# RC_Interface.net
KiCad netlist of a schematic drawn in Altium Designer
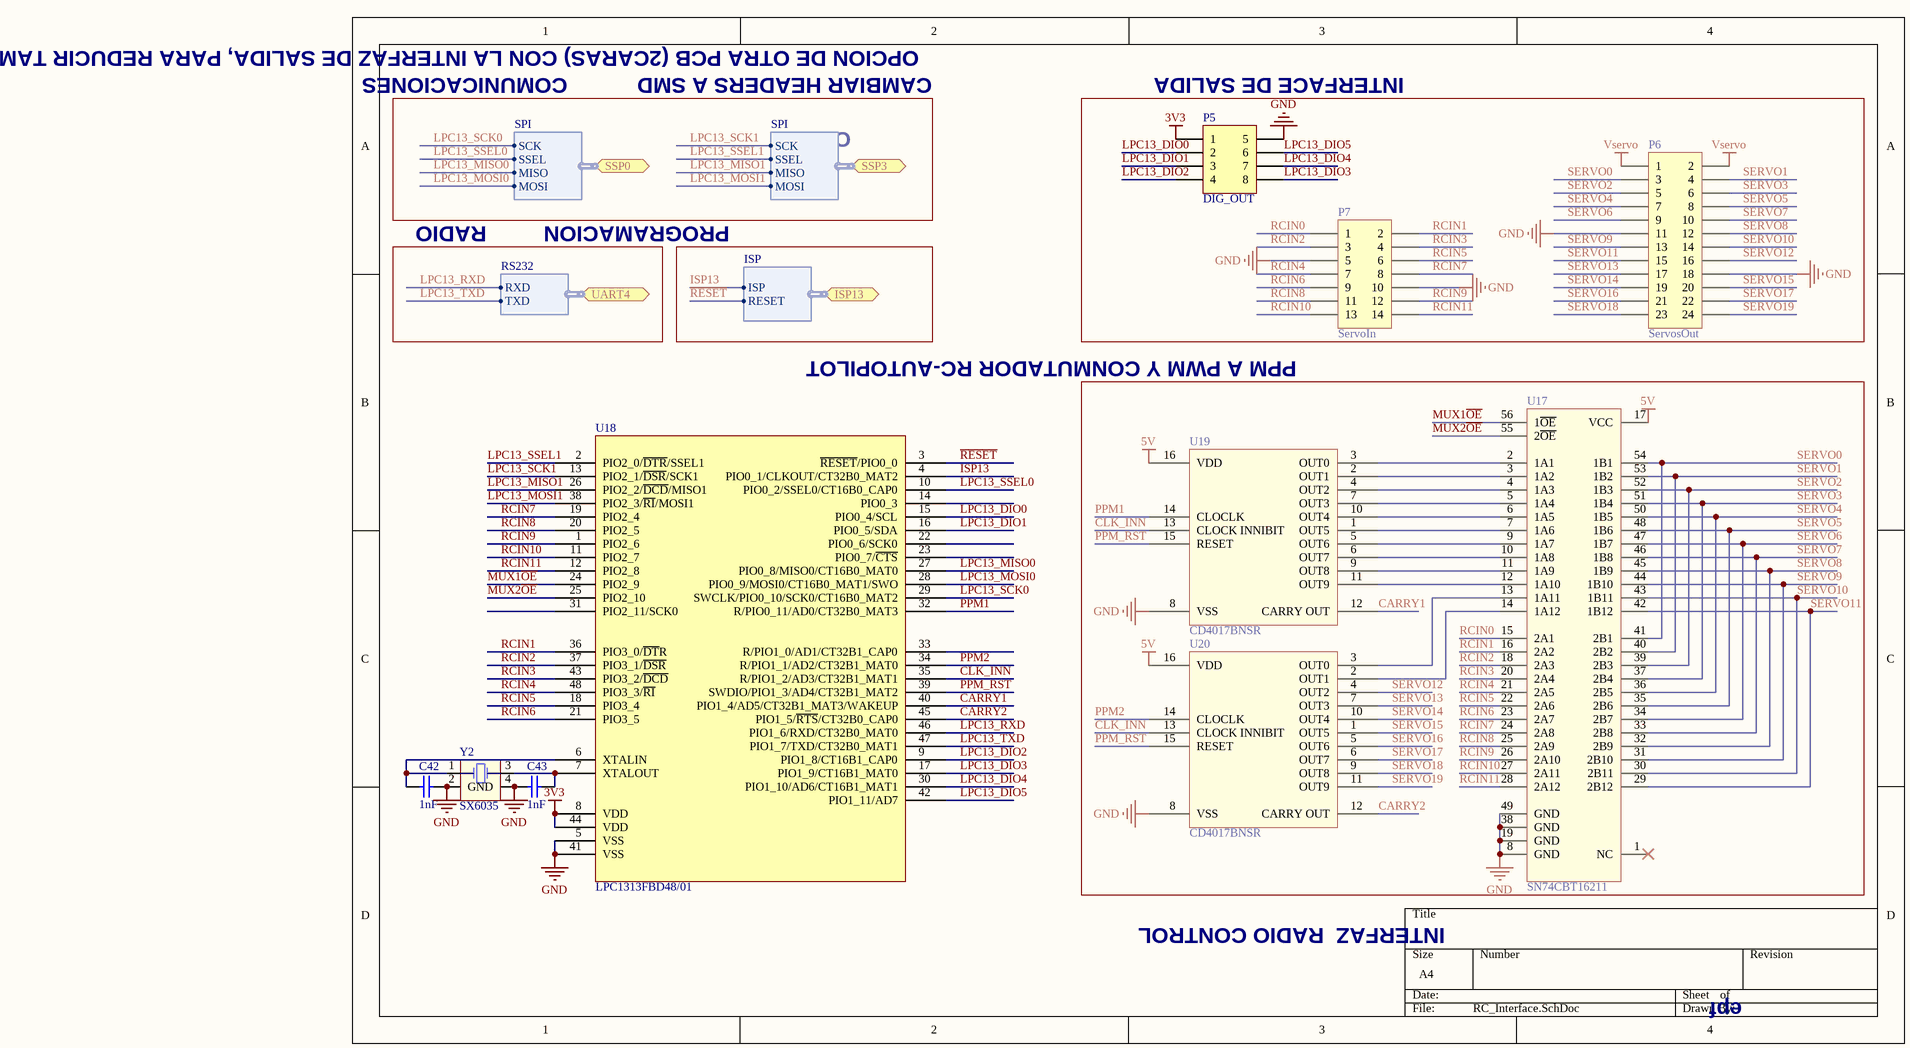
[diagram p0: RC_Interface.SchDoc]

(export (version "E")
  (design (tool "Eeschema 10.0.6"))
  (components
    (comp (ref "C42")
      (value "1nF")
      (footprint "CAP0402")
      (fields (field (name "Comment") "Capacitor"))
      (libsource (lib "epf") (part "Cap"))
    )
    (comp (ref "C43")
      (value "1nF")
      (footprint "CAP0402")
      (fields (field (name "Comment") "Capacitor"))
      (libsource (lib "epf") (part "Cap"))
    )
    (comp (ref "P5")
      (value "DIG_OUT")
      (footprint "HDR2X4_CEN")
      (description "Header, 4-Pin, Dual row")
      (fields (field (name "PUBLISHER") "Altium Limited"))
      (libsource (lib "epf") (part "AP_SALIDA_DIGITAL"))
    )
    (comp (ref "P6")
      (value "ServosOut")
      (footprint "HDR 2X12")
      (description "Header, 12-Pin, Dual row")
      (fields (field (name "PUBLISHER") "Altium Limited"))
      (libsource (lib "epf") (part "ServosOut"))
    )
    (comp (ref "P7")
      (value "ServoIn")
      (footprint "HDR2X7")
      (description "Header, 7-Pin, Dual row")
      (fields (field (name "PUBLISHER") "Altium Limited"))
      (libsource (lib "epf") (part "ServoIn"))
    )
    (comp (ref "U17")
      (value "SN74CBT16211")
      (footprint "SOP635P1035-56N")
      (description "MUX")
      (libsource (lib "epf") (part "SN74CBT16211"))
    )
    (comp (ref "U18")
      (value "LPC1313FBD48/01")
      (footprint "TQFP48_LPC1343")
      (description "ARM CortexM3 32K Flash, 8k RAM")
      (libsource (lib "epf") (part "LPC1313FBD48/01"))
    )
    (comp (ref "U19")
      (value "CD4017BNSR")
      (footprint "SOIC127P602-16BN")
      (description "COUNTER/DIVIDERS")
      (libsource (lib "epf") (part "CD4017BNSR"))
    )
    (comp (ref "U20")
      (value "CD4017BNSR")
      (footprint "SOIC127P602-16BN")
      (description "COUNTER/DIVIDERS")
      (libsource (lib "epf") (part "CD4017BNSR"))
    )
    (comp (ref "Y2") (value "SX6035") (footprint "SX6035") (libsource (lib "epf") (part "XTAL_SX6035")))
  )
  (nets
    (net (code "4") (name "/CARRY1") (class "Default")
      (node (ref "U18") (pin "40") (pinfunction "PIO1_4/AD5/CT32B1_MAT3/WAKEUP_40") (pintype "passive"))
      (node (ref "U19") (pin "12") (pinfunction "CARRY_OUT_12") (pintype "passive"))
    )
    (net (code "5") (name "/CARRY2") (class "Default")
      (node (ref "U18") (pin "45") (pinfunction "PIO1_5/~{RTS}/CT32B0_CAP0_45") (pintype "passive"))
      (node (ref "U20") (pin "12") (pinfunction "CARRY_OUT_12") (pintype "passive"))
    )
    (net (code "6") (name "/CLK_INN") (class "Default")
      (node (ref "U18") (pin "35") (pinfunction "R/PIO1_2/AD3/CT32B1_MAT1_35") (pintype "passive"))
      (node (ref "U19") (pin "13") (pinfunction "CLOCK_INNIBIT_13") (pintype "passive"))
      (node (ref "U20") (pin "13") (pinfunction "CLOCK_INNIBIT_13") (pintype "passive"))
    )
    (net (code "7") (name "/ISP13") (class "Default")
      (node (ref "U18") (pin "4") (pinfunction "PIO0_1/CLKOUT/CT32B0_MAT2_4") (pintype "passive"))
    )
    (net (code "8") (name "/LPC13_DIO0") (class "Default")
      (node (ref "P5") (pin "2") (pinfunction "2_2") (pintype "passive"))
      (node (ref "U18") (pin "15") (pinfunction "PIO0_4/SCL_15") (pintype "passive"))
    )
    (net (code "9") (name "/LPC13_DIO1") (class "Default")
      (node (ref "P5") (pin "3") (pinfunction "3_3") (pintype "passive"))
      (node (ref "U18") (pin "16") (pinfunction "PIO0_5/SDA_16") (pintype "passive"))
    )
    (net (code "10") (name "/LPC13_DIO2") (class "Default")
      (node (ref "P5") (pin "4") (pinfunction "4_4") (pintype "passive"))
      (node (ref "U18") (pin "9") (pinfunction "PIO1_8/CT16B1_CAP0_9") (pintype "passive"))
    )
    (net (code "11") (name "/LPC13_DIO3") (class "Default")
      (node (ref "P5") (pin "8") (pinfunction "8_8") (pintype "passive"))
      (node (ref "U18") (pin "17") (pinfunction "PIO1_9/CT16B1_MAT0_17") (pintype "passive"))
    )
    (net (code "12") (name "/LPC13_DIO4") (class "Default")
      (node (ref "P5") (pin "7") (pinfunction "7_7") (pintype "passive"))
      (node (ref "U18") (pin "30") (pinfunction "PIO1_10/AD6/CT16B1_MAT1_30") (pintype "passive"))
    )
    (net (code "13") (name "/LPC13_DIO5") (class "Default")
      (node (ref "P5") (pin "6") (pinfunction "6_6") (pintype "passive"))
      (node (ref "U18") (pin "42") (pinfunction "PIO1_11/AD7_42") (pintype "passive"))
    )
    (net (code "14") (name "/LPC13_MISO0") (class "Default")
      (node (ref "U18") (pin "27") (pinfunction "PIO0_8/MISO0/CT16B0_MAT0_27") (pintype "passive"))
    )
    (net (code "15") (name "/LPC13_MISO1") (class "Default")
      (node (ref "U18") (pin "26") (pinfunction "PIO2_2/~{DCD}/MISO1_26") (pintype "passive"))
    )
    (net (code "16") (name "/LPC13_MOSI0") (class "Default")
      (node (ref "U18") (pin "28") (pinfunction "PIO0_9/MOSI0/CT16B0_MAT1/SWO_28") (pintype "passive"))
    )
    (net (code "17") (name "/LPC13_MOSI1") (class "Default")
      (node (ref "U18") (pin "38") (pinfunction "PIO2_3/~{RI}/MOSI1_38") (pintype "passive"))
    )
    (net (code "18") (name "/LPC13_RXD") (class "Default")
      (node (ref "U18") (pin "46") (pinfunction "PIO1_6/RXD/CT32B0_MAT0_46") (pintype "passive"))
    )
    (net (code "19") (name "/LPC13_SCK0") (class "Default")
      (node (ref "U18") (pin "29") (pinfunction "SWCLK/PIO0_10/SCK0/CT16B0_MAT2_29") (pintype "passive"))
    )
    (net (code "20") (name "/LPC13_SCK1") (class "Default")
      (node (ref "U18") (pin "13") (pinfunction "PIO2_1/~{DSR}/SCK1_13") (pintype "passive"))
    )
    (net (code "21") (name "/LPC13_SSEL0") (class "Default")
      (node (ref "U18") (pin "10") (pinfunction "PIO0_2/SSEL0/CT16B0_CAP0_10") (pintype "passive"))
    )
    (net (code "22") (name "/LPC13_SSEL1") (class "Default")
      (node (ref "U18") (pin "2") (pinfunction "PIO2_0/~{DTR}/SSEL1_2") (pintype "passive"))
    )
    (net (code "23") (name "/LPC13_TXD") (class "Default")
      (node (ref "U18") (pin "47") (pinfunction "PIO1_7/TXD/CT32B0_MAT1_47") (pintype "passive"))
    )
    (net (code "24") (name "/MUX1~{OE}") (class "Default")
      (node (ref "U17") (pin "56") (pinfunction "1~{OE}_56") (pintype "passive"))
      (node (ref "U18") (pin "24") (pinfunction "PIO2_9_24") (pintype "passive"))
    )
    (net (code "25") (name "/MUX2~{OE}") (class "Default")
      (node (ref "U17") (pin "55") (pinfunction "2~{OE}_55") (pintype "passive"))
      (node (ref "U18") (pin "25") (pinfunction "PIO2_10_25") (pintype "passive"))
    )
    (net (code "26") (name "/PPM1") (class "Default")
      (node (ref "U18") (pin "32") (pinfunction "R/PIO0_11/AD0/CT32B0_MAT3_32") (pintype "passive"))
      (node (ref "U19") (pin "14") (pinfunction "CLOCLK_14") (pintype "passive"))
    )
    (net (code "27") (name "/PPM2") (class "Default")
      (node (ref "U18") (pin "34") (pinfunction "R/PIO1_1/AD2/CT32B1_MAT0_34") (pintype "passive"))
      (node (ref "U20") (pin "14") (pinfunction "CLOCLK_14") (pintype "passive"))
    )
    (net (code "28") (name "/PPM_RST") (class "Default")
      (node (ref "U18") (pin "39") (pinfunction "SWDIO/PIO1_3/AD4/CT32B1_MAT2_39") (pintype "passive"))
      (node (ref "U19") (pin "15") (pinfunction "RESET_15") (pintype "passive"))
      (node (ref "U20") (pin "15") (pinfunction "RESET_15") (pintype "passive"))
    )
    (net (code "29") (name "/RCIN0") (class "Default")
      (node (ref "P7") (pin "1") (pinfunction "1_1") (pintype "passive"))
      (node (ref "U17") (pin "15") (pinfunction "2A1_15") (pintype "passive"))
    )
    (net (code "30") (name "/RCIN1") (class "Default")
      (node (ref "P7") (pin "2") (pinfunction "2_2") (pintype "passive"))
      (node (ref "U17") (pin "16") (pinfunction "2A2_16") (pintype "passive"))
      (node (ref "U18") (pin "36") (pinfunction "PIO3_0/~{DT}R_36") (pintype "passive"))
    )
    (net (code "31") (name "/RCIN2") (class "Default")
      (node (ref "P7") (pin "3") (pinfunction "3_3") (pintype "passive"))
      (node (ref "U17") (pin "18") (pinfunction "2A3_18") (pintype "passive"))
      (node (ref "U18") (pin "37") (pinfunction "PIO3_1/~{DSR}_37") (pintype "passive"))
    )
    (net (code "32") (name "/RCIN3") (class "Default")
      (node (ref "P7") (pin "4") (pinfunction "4_4") (pintype "passive"))
      (node (ref "U17") (pin "20") (pinfunction "2A4_20") (pintype "passive"))
      (node (ref "U18") (pin "43") (pinfunction "PIO3_2/~{DCD}_43") (pintype "passive"))
    )
    (net (code "33") (name "/RCIN4") (class "Default")
      (node (ref "P7") (pin "7") (pinfunction "7_7") (pintype "passive"))
      (node (ref "U17") (pin "21") (pinfunction "2A5_21") (pintype "passive"))
      (node (ref "U18") (pin "48") (pinfunction "PIO3_3/~{RI}_48") (pintype "passive"))
    )
    (net (code "34") (name "/RCIN5") (class "Default")
      (node (ref "P7") (pin "6") (pinfunction "6_6") (pintype "passive"))
      (node (ref "U17") (pin "22") (pinfunction "2A6_22") (pintype "passive"))
      (node (ref "U18") (pin "18") (pinfunction "PIO3_4_18") (pintype "passive"))
    )
    (net (code "35") (name "/RCIN6") (class "Default")
      (node (ref "P7") (pin "9") (pinfunction "9_9") (pintype "passive"))
      (node (ref "U17") (pin "23") (pinfunction "2A7_23") (pintype "passive"))
      (node (ref "U18") (pin "21") (pinfunction "PIO3_5_21") (pintype "passive"))
    )
    (net (code "36") (name "/RCIN7") (class "Default")
      (node (ref "P7") (pin "8") (pinfunction "8_8") (pintype "passive"))
      (node (ref "U17") (pin "24") (pinfunction "2A8_24") (pintype "passive"))
      (node (ref "U18") (pin "19") (pinfunction "PIO2_4_19") (pintype "passive"))
    )
    (net (code "37") (name "/RCIN8") (class "Default")
      (node (ref "P7") (pin "11") (pinfunction "11_11") (pintype "passive"))
      (node (ref "U17") (pin "25") (pinfunction "2A9_25") (pintype "passive"))
      (node (ref "U18") (pin "20") (pinfunction "PIO2_5_20") (pintype "passive"))
    )
    (net (code "38") (name "/RCIN9") (class "Default")
      (node (ref "P7") (pin "12") (pinfunction "12_12") (pintype "passive"))
      (node (ref "U17") (pin "26") (pinfunction "2A10_26") (pintype "passive"))
      (node (ref "U18") (pin "1") (pinfunction "PIO2_6_1") (pintype "passive"))
    )
    (net (code "39") (name "/RCIN10") (class "Default")
      (node (ref "P7") (pin "13") (pinfunction "13_13") (pintype "passive"))
      (node (ref "U17") (pin "27") (pinfunction "2A11_27") (pintype "passive"))
      (node (ref "U18") (pin "11") (pinfunction "PIO2_7_11") (pintype "passive"))
    )
    (net (code "40") (name "/RCIN11") (class "Default")
      (node (ref "P7") (pin "14") (pinfunction "14_14") (pintype "passive"))
      (node (ref "U17") (pin "28") (pinfunction "2A12_28") (pintype "passive"))
      (node (ref "U18") (pin "12") (pinfunction "PIO2_8_12") (pintype "passive"))
    )
    (net (code "41") (name "/RESET") (class "Default")
      (node (ref "U18") (pin "3") (pinfunction "~{RESET}/PIO0_0_3") (pintype "passive"))
    )
    (net (code "42") (name "/SERVO0") (class "Default")
      (node (ref "P6") (pin "3") (pinfunction "3_3") (pintype "passive"))
      (node (ref "U17") (pin "41") (pinfunction "2B1_41") (pintype "passive"))
      (node (ref "U17") (pin "54") (pinfunction "1B1_54") (pintype "passive"))
    )
    (net (code "43") (name "/SERVO1") (class "Default")
      (node (ref "P6") (pin "4") (pinfunction "4_4") (pintype "passive"))
      (node (ref "U17") (pin "40") (pinfunction "2B2_40") (pintype "passive"))
      (node (ref "U17") (pin "53") (pinfunction "1B2_53") (pintype "passive"))
    )
    (net (code "44") (name "/SERVO2") (class "Default")
      (node (ref "P6") (pin "5") (pinfunction "5_5") (pintype "passive"))
      (node (ref "U17") (pin "39") (pinfunction "2B3_39") (pintype "passive"))
      (node (ref "U17") (pin "52") (pinfunction "1B3_52") (pintype "passive"))
    )
    (net (code "45") (name "/SERVO3") (class "Default")
      (node (ref "P6") (pin "6") (pinfunction "6_6") (pintype "passive"))
      (node (ref "U17") (pin "37") (pinfunction "2B4_37") (pintype "passive"))
      (node (ref "U17") (pin "51") (pinfunction "1B4_51") (pintype "passive"))
    )
    (net (code "46") (name "/SERVO4") (class "Default")
      (node (ref "P6") (pin "7") (pinfunction "7_7") (pintype "passive"))
      (node (ref "U17") (pin "36") (pinfunction "2B5_36") (pintype "passive"))
      (node (ref "U17") (pin "50") (pinfunction "1B5_50") (pintype "passive"))
    )
    (net (code "47") (name "/SERVO5") (class "Default")
      (node (ref "P6") (pin "8") (pinfunction "8_8") (pintype "passive"))
      (node (ref "U17") (pin "35") (pinfunction "2B6_35") (pintype "passive"))
      (node (ref "U17") (pin "48") (pinfunction "1B6_48") (pintype "passive"))
    )
    (net (code "48") (name "/SERVO6") (class "Default")
      (node (ref "P6") (pin "9") (pinfunction "9_9") (pintype "passive"))
      (node (ref "U17") (pin "34") (pinfunction "2B7_34") (pintype "passive"))
      (node (ref "U17") (pin "47") (pinfunction "1B7_47") (pintype "passive"))
    )
    (net (code "49") (name "/SERVO7") (class "Default")
      (node (ref "P6") (pin "10") (pinfunction "10_10") (pintype "passive"))
      (node (ref "U17") (pin "33") (pinfunction "2B8_33") (pintype "passive"))
      (node (ref "U17") (pin "46") (pinfunction "1B8_46") (pintype "passive"))
    )
    (net (code "50") (name "/SERVO8") (class "Default")
      (node (ref "P6") (pin "12") (pinfunction "12_12") (pintype "passive"))
      (node (ref "U17") (pin "32") (pinfunction "2B9_32") (pintype "passive"))
      (node (ref "U17") (pin "45") (pinfunction "1B9_45") (pintype "passive"))
    )
    (net (code "51") (name "/SERVO9") (class "Default")
      (node (ref "P6") (pin "13") (pinfunction "13_13") (pintype "passive"))
      (node (ref "U17") (pin "31") (pinfunction "2B10_31") (pintype "passive"))
      (node (ref "U17") (pin "44") (pinfunction "1B10_44") (pintype "passive"))
    )
    (net (code "52") (name "/SERVO10") (class "Default")
      (node (ref "P6") (pin "14") (pinfunction "14_14") (pintype "passive"))
      (node (ref "U17") (pin "30") (pinfunction "2B11_30") (pintype "passive"))
      (node (ref "U17") (pin "43") (pinfunction "1B11_43") (pintype "passive"))
    )
    (net (code "53") (name "/SERVO11") (class "Default")
      (node (ref "P6") (pin "15") (pinfunction "15_15") (pintype "passive"))
      (node (ref "U17") (pin "29") (pinfunction "2B12_29") (pintype "passive"))
      (node (ref "U17") (pin "42") (pinfunction "1B12_42") (pintype "passive"))
    )
    (net (code "54") (name "/SERVO12") (class "Default")
      (node (ref "P6") (pin "16") (pinfunction "16_16") (pintype "passive"))
      (node (ref "U20") (pin "4") (pinfunction "OUT2_4") (pintype "passive"))
    )
    (net (code "55") (name "/SERVO13") (class "Default")
      (node (ref "P6") (pin "17") (pinfunction "17_17") (pintype "passive"))
      (node (ref "U20") (pin "7") (pinfunction "OUT3_7") (pintype "passive"))
    )
    (net (code "56") (name "/SERVO14") (class "Default")
      (node (ref "P6") (pin "19") (pinfunction "19_19") (pintype "passive"))
      (node (ref "U20") (pin "10") (pinfunction "OUT4_10") (pintype "passive"))
    )
    (net (code "57") (name "/SERVO15") (class "Default")
      (node (ref "P6") (pin "20") (pinfunction "20_20") (pintype "passive"))
      (node (ref "U20") (pin "1") (pinfunction "OUT5_1") (pintype "passive"))
    )
    (net (code "58") (name "/SERVO16") (class "Default")
      (node (ref "P6") (pin "21") (pinfunction "21_21") (pintype "passive"))
      (node (ref "U20") (pin "5") (pinfunction "OUT6_5") (pintype "passive"))
    )
    (net (code "59") (name "/SERVO17") (class "Default")
      (node (ref "P6") (pin "22") (pinfunction "22_22") (pintype "passive"))
      (node (ref "U20") (pin "6") (pinfunction "OUT7_6") (pintype "passive"))
    )
    (net (code "60") (name "/SERVO18") (class "Default")
      (node (ref "P6") (pin "23") (pinfunction "23_23") (pintype "passive"))
      (node (ref "U20") (pin "9") (pinfunction "OUT8_9") (pintype "passive"))
    )
    (net (code "61") (name "/SERVO19") (class "Default")
      (node (ref "P6") (pin "24") (pinfunction "24_24") (pintype "passive"))
      (node (ref "U20") (pin "11") (pinfunction "OUT9_11") (pintype "passive"))
    )
    (net (code "65") (name "3V3") (class "Default")
      (node (ref "P5") (pin "1") (pinfunction "1_1") (pintype "passive"))
      (node (ref "U18") (pin "44") (pinfunction "VDD_44") (pintype "passive"))
      (node (ref "U18") (pin "8") (pinfunction "VDD_8") (pintype "passive"))
    )
    (net (code "66") (name "5V") (class "Default")
      (node (ref "U17") (pin "17") (pinfunction "VCC_17") (pintype "passive"))
      (node (ref "U19") (pin "16") (pinfunction "VDD_16") (pintype "passive"))
      (node (ref "U20") (pin "16") (pinfunction "VDD_16") (pintype "passive"))
    )
    (net (code "67") (name "GND") (class "Default")
      (node (ref "C42") (pin "1") (pinfunction "1_1") (pintype "passive"))
      (node (ref "C43") (pin "2") (pinfunction "2_2") (pintype "passive"))
      (node (ref "P5") (pin "5") (pinfunction "5_5") (pintype "passive"))
      (node (ref "P6") (pin "11") (pinfunction "11_11") (pintype "passive"))
      (node (ref "P6") (pin "18") (pinfunction "18_18") (pintype "passive"))
      (node (ref "P7") (pin "10") (pinfunction "10_10") (pintype "passive"))
      (node (ref "P7") (pin "5") (pinfunction "5_5") (pintype "passive"))
      (node (ref "U17") (pin "19") (pinfunction "GND_19") (pintype "passive"))
      (node (ref "U17") (pin "38") (pinfunction "GND_38") (pintype "passive"))
      (node (ref "U17") (pin "49") (pinfunction "GND_49") (pintype "passive"))
      (node (ref "U17") (pin "8") (pinfunction "GND_8") (pintype "passive"))
      (node (ref "U18") (pin "41") (pinfunction "VSS_41") (pintype "passive"))
      (node (ref "U18") (pin "5") (pinfunction "VSS_5") (pintype "passive"))
      (node (ref "U19") (pin "8") (pinfunction "VSS_8") (pintype "passive"))
      (node (ref "U20") (pin "8") (pinfunction "VSS_8") (pintype "passive"))
      (node (ref "Y2") (pin "2") (pinfunction "GND_2") (pintype "passive"))
      (node (ref "Y2") (pin "4") (pinfunction "GND_4") (pintype "passive"))
    )
    (net (code "68") (name "Net-(U17-1A1)") (class "Default")
      (node (ref "U17") (pin "2") (pinfunction "1A1_2") (pintype "passive"))
      (node (ref "U19") (pin "3") (pinfunction "OUT0_3") (pintype "passive"))
    )
    (net (code "69") (name "Net-(U17-1A2)") (class "Default")
      (node (ref "U17") (pin "3") (pinfunction "1A2_3") (pintype "passive"))
      (node (ref "U19") (pin "2") (pinfunction "OUT1_2") (pintype "passive"))
    )
    (net (code "70") (name "Net-(U17-1A3)") (class "Default")
      (node (ref "U17") (pin "4") (pinfunction "1A3_4") (pintype "passive"))
      (node (ref "U19") (pin "4") (pinfunction "OUT2_4") (pintype "passive"))
    )
    (net (code "71") (name "Net-(U17-1A4)") (class "Default")
      (node (ref "U17") (pin "5") (pinfunction "1A4_5") (pintype "passive"))
      (node (ref "U19") (pin "7") (pinfunction "OUT3_7") (pintype "passive"))
    )
    (net (code "72") (name "Net-(U17-1A5)") (class "Default")
      (node (ref "U17") (pin "6") (pinfunction "1A5_6") (pintype "passive"))
      (node (ref "U19") (pin "10") (pinfunction "OUT4_10") (pintype "passive"))
    )
    (net (code "73") (name "Net-(U17-1A6)") (class "Default")
      (node (ref "U17") (pin "7") (pinfunction "1A6_7") (pintype "passive"))
      (node (ref "U19") (pin "1") (pinfunction "OUT5_1") (pintype "passive"))
    )
    (net (code "74") (name "Net-(U17-1A7)") (class "Default")
      (node (ref "U17") (pin "9") (pinfunction "1A7_9") (pintype "passive"))
      (node (ref "U19") (pin "5") (pinfunction "OUT6_5") (pintype "passive"))
    )
    (net (code "75") (name "Net-(U17-1A8)") (class "Default")
      (node (ref "U17") (pin "10") (pinfunction "1A8_10") (pintype "passive"))
      (node (ref "U19") (pin "6") (pinfunction "OUT7_6") (pintype "passive"))
    )
    (net (code "76") (name "Net-(U17-1A9)") (class "Default")
      (node (ref "U17") (pin "11") (pinfunction "1A9_11") (pintype "passive"))
      (node (ref "U19") (pin "9") (pinfunction "OUT8_9") (pintype "passive"))
    )
    (net (code "77") (name "Net-(U17-1A10)") (class "Default")
      (node (ref "U17") (pin "12") (pinfunction "1A10_12") (pintype "passive"))
      (node (ref "U19") (pin "11") (pinfunction "OUT9_11") (pintype "passive"))
    )
    (net (code "78") (name "Net-(U17-1A11)") (class "Default")
      (node (ref "U17") (pin "13") (pinfunction "1A11_13") (pintype "passive"))
      (node (ref "U20") (pin "3") (pinfunction "OUT0_3") (pintype "passive"))
    )
    (net (code "79") (name "Net-(U17-1A12)") (class "Default")
      (node (ref "U17") (pin "14") (pinfunction "1A12_14") (pintype "passive"))
      (node (ref "U20") (pin "2") (pinfunction "OUT1_2") (pintype "passive"))
    )
    (net (code "80") (name "Net-(U18-XTALIN)") (class "Default")
      (node (ref "C42") (pin "2") (pinfunction "2_2") (pintype "passive"))
      (node (ref "U18") (pin "6") (pinfunction "XTALIN_6") (pintype "passive"))
      (node (ref "Y2") (pin "1") (pinfunction "XTAL_1") (pintype "passive"))
    )
    (net (code "81") (name "Net-(U18-XTALOUT)") (class "Default")
      (node (ref "C43") (pin "1") (pinfunction "1_1") (pintype "passive"))
      (node (ref "U18") (pin "7") (pinfunction "XTALOUT_7") (pintype "passive"))
      (node (ref "Y2") (pin "3") (pinfunction "XTAL_3") (pintype "passive"))
    )
    (net (code "82") (name "Vservo") (class "Default")
      (node (ref "P6") (pin "1") (pinfunction "1_1") (pintype "passive"))
      (node (ref "P6") (pin "2") (pinfunction "2_2") (pintype "passive"))
    )
    (net (code "83") (name "unconnected-(U17-NC-Pad1)") (class "Default")
      (node (ref "U17") (pin "1") (pinfunction "NC_1") (pintype "passive+no_connect"))
    )
    (net (code "84") (name "unconnected-(U18-PIO0_3-Pad14)") (class "Default")
      (node (ref "U18") (pin "14") (pinfunction "PIO0_3_14") (pintype "passive"))
    )
    (net (code "85") (name "unconnected-(U18-PIO0_6{slash}SCK0-Pad22)") (class "Default")
      (node (ref "U18") (pin "22") (pinfunction "PIO0_6/SCK0_22") (pintype "passive"))
    )
    (net (code "86") (name "unconnected-(U18-PIO0_7{slash}~{CTS}-Pad23)") (class "Default")
      (node (ref "U18") (pin "23") (pinfunction "PIO0_7/~{CTS}_23") (pintype "passive"))
    )
    (net (code "87") (name "unconnected-(U18-PIO2_11{slash}SCK0-Pad31)") (class "Default")
      (node (ref "U18") (pin "31") (pinfunction "PIO2_11/SCK0_31") (pintype "passive"))
    )
    (net (code "88") (name "unconnected-(U18-R{slash}PIO1_0{slash}AD1{slash}CT32B1_CAP0-Pad33)") (class "Default")
      (node (ref "U18") (pin "33") (pinfunction "R/PIO1_0/AD1/CT32B1_CAP0_33") (pintype "passive"))
    )
  )
)
